# QCopterFC_KEY_Sch.net
KiCad netlist of a schematic drawn in Altium Designer
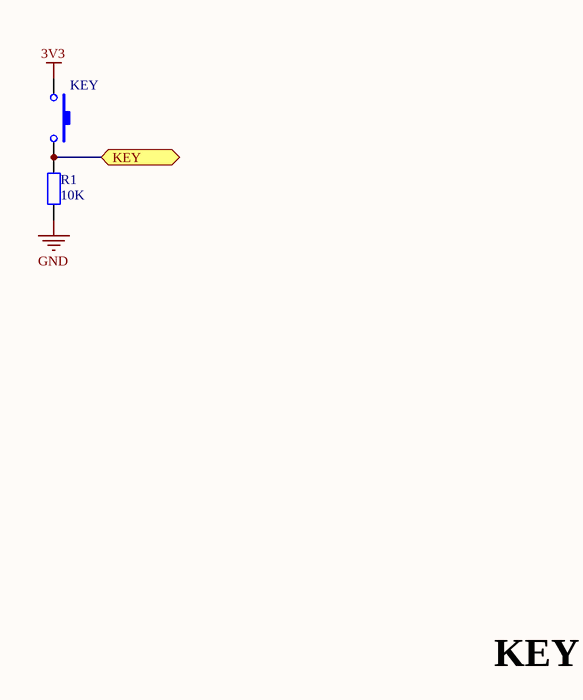
[diagram p0: QCopterFC_KEY_Sch.SchDoc]

(export (version "E")
  (design (tool "Eeschema 10.0.6"))
  (components
    (comp (ref "KEY")
      (value "SW-PB_1")
      (footprint "PCB_Switch:BT_90_T")
      (description "Switch")
      (fields (field (name "PUBLISHER") "Altium Limited"))
      (libsource (lib "SCH_Switch") (part "SW-PB_1"))
    )
    (comp (ref "R1")
      (value "10K")
      (footprint "PCB_Passive:RES_0603")
      (description "Resistor")
      (fields (field (name "Comment") "Res_0603"))
      (libsource (lib "SCH_Passive") (part "Res_0603"))
    )
  )
  (nets
    (net (code "1") (name "/KEY") (class "Default")
      (node (ref "KEY") (pin "2") (pinfunction "2_2") (pintype "passive"))
      (node (ref "R1") (pin "2") (pinfunction "2_2") (pintype "passive"))
    )
    (net (code "2") (name "3V3") (class "Default")
      (node (ref "KEY") (pin "1") (pinfunction "1_1") (pintype "passive"))
    )
    (net (code "3") (name "GND") (class "Default")
      (node (ref "R1") (pin "1") (pinfunction "1_1") (pintype "passive"))
    )
  )
)
